# RS232.net
KiCad netlist of a schematic drawn in Altium Designer
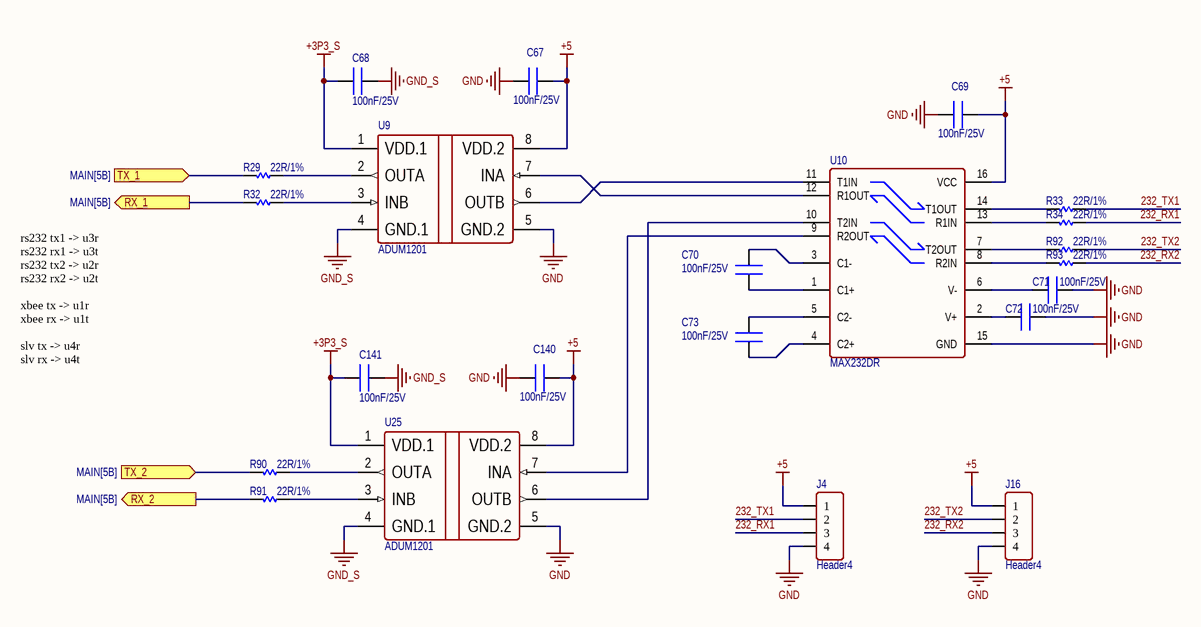
[diagram p0: RS232.SchDoc]

(export (version "E")
  (design (tool "Eeschema 10.0.6"))
  (components
    (comp (ref "C67")
      (value "100nF/25V")
      (footprint "CN-SMD-0603")
      (description "CAP CER 0.1UF 25V X7R 0603")
      (libsource (lib "Library") (part "CN"))
    )
    (comp (ref "C68")
      (value "100nF/25V")
      (footprint "CN-SMD-0603")
      (description "CAP CER 0.1UF 25V X7R 0603")
      (libsource (lib "Library") (part "CN"))
    )
    (comp (ref "C69")
      (value "100nF/25V")
      (footprint "CN-SMD-0603")
      (description "CAP CER 0.1UF 25V X7R 0603")
      (libsource (lib "Library") (part "CN"))
    )
    (comp (ref "C70")
      (value "100nF/25V")
      (footprint "CN-SMD-0603")
      (description "CAP CER 0.1UF 25V X7R 0603")
      (libsource (lib "Library") (part "CN"))
    )
    (comp (ref "C71")
      (value "100nF/25V")
      (footprint "CN-SMD-0603")
      (description "CAP CER 0.1UF 25V X7R 0603")
      (libsource (lib "Library") (part "CN"))
    )
    (comp (ref "C72")
      (value "100nF/25V")
      (footprint "CN-SMD-0603")
      (description "CAP CER 0.1UF 25V X7R 0603")
      (libsource (lib "Library") (part "CN"))
    )
    (comp (ref "C73")
      (value "100nF/25V")
      (footprint "CN-SMD-0603")
      (description "CAP CER 0.1UF 25V X7R 0603")
      (libsource (lib "Library") (part "CN"))
    )
    (comp (ref "C140")
      (value "100nF/25V")
      (footprint "CN-SMD-0603")
      (description "CAP CER 0.1UF 25V X7R 0603")
      (libsource (lib "Library") (part "CN"))
    )
    (comp (ref "C141")
      (value "100nF/25V")
      (footprint "CN-SMD-0603")
      (description "CAP CER 0.1UF 25V X7R 0603")
      (libsource (lib "Library") (part "CN"))
    )
    (comp (ref "J4")
      (value "Header4")
      (footprint "XH2.54-4-DIP")
      (description "Connector 4")
      (fields
        (field (name "MANUFACTURER") "Würth Elektronik eiSos GmbH")
        (field (name "PARTNO") "613002143121")
        (field (name "CREATED BY") "Karrer Zheng")
      )
      (libsource (lib "Library") (part "Header4"))
    )
    (comp (ref "J16")
      (value "Header4")
      (footprint "XH2.54-4-DIP")
      (description "Connector 4")
      (fields
        (field (name "MANUFACTURER") "Würth Elektronik eiSos GmbH")
        (field (name "PARTNO") "613002143121")
        (field (name "CREATED BY") "Karrer Zheng")
      )
      (libsource (lib "Library") (part "Header4"))
    )
    (comp (ref "R29")
      (value "22R/1%")
      (footprint "RES-SMD-0603")
      (description "RES SMD 22 OHM 1% 1/10W 0603")
      (libsource (lib "Library") (part "Res-SMD"))
    )
    (comp (ref "R32")
      (value "22R/1%")
      (footprint "RES-SMD-0603")
      (description "RES SMD 22 OHM 1% 1/10W 0603")
      (libsource (lib "Library") (part "Res-SMD"))
    )
    (comp (ref "R33")
      (value "22R/1%")
      (footprint "RES-SMD-0603")
      (description "RES SMD 22 OHM 1% 1/10W 0603")
      (libsource (lib "Library") (part "Res-SMD"))
    )
    (comp (ref "R34")
      (value "22R/1%")
      (footprint "RES-SMD-0603")
      (description "RES SMD 22 OHM 1% 1/10W 0603")
      (libsource (lib "Library") (part "Res-SMD"))
    )
    (comp (ref "R90")
      (value "22R/1%")
      (footprint "RES-SMD-0603")
      (description "RES SMD 22 OHM 1% 1/10W 0603")
      (libsource (lib "Library") (part "Res-SMD"))
    )
    (comp (ref "R91")
      (value "22R/1%")
      (footprint "RES-SMD-0603")
      (description "RES SMD 22 OHM 1% 1/10W 0603")
      (libsource (lib "Library") (part "Res-SMD"))
    )
    (comp (ref "R92")
      (value "22R/1%")
      (footprint "RES-SMD-0603")
      (description "RES SMD 22 OHM 1% 1/10W 0603")
      (libsource (lib "Library") (part "Res-SMD"))
    )
    (comp (ref "R93")
      (value "22R/1%")
      (footprint "RES-SMD-0603")
      (description "RES SMD 22 OHM 1% 1/10W 0603")
      (libsource (lib "Library") (part "Res-SMD"))
    )
    (comp (ref "U9")
      (value "ADUM1201")
      (footprint "SO8")
      (description "DGTL ISOLTR 2.5KV 2CH GP 8-SOIC")
      (libsource (lib "Library") (part "ADUM1201"))
    )
    (comp (ref "U10")
      (value "MAX232DR")
      (footprint "SO16")
      (description "IC TRANSCEIVER FULL 2/2 16SOIC")
      (libsource (lib "Library") (part "MAX3232"))
    )
    (comp (ref "U25")
      (value "ADUM1201")
      (footprint "SO8")
      (description "DGTL ISOLTR 2.5KV 2CH GP 8-SOIC")
      (libsource (lib "Library") (part "ADUM1201"))
    )
  )
  (nets
    (net (code "1") (name "+3P3_S") (class "Default")
      (node (ref "C141") (pin "2") (pinfunction "2_2") (pintype "passive"))
      (node (ref "C68") (pin "2") (pinfunction "2_2") (pintype "passive"))
      (node (ref "U25") (pin "1") (pinfunction "VDD.1_1") (pintype "passive"))
      (node (ref "U9") (pin "1") (pinfunction "VDD.1_1") (pintype "passive"))
    )
    (net (code "2") (name "+5") (class "Default")
      (node (ref "C140") (pin "1") (pinfunction "1_1") (pintype "passive"))
      (node (ref "C67") (pin "1") (pinfunction "1_1") (pintype "passive"))
      (node (ref "C69") (pin "1") (pinfunction "1_1") (pintype "passive"))
      (node (ref "J16") (pin "1") (pinfunction "1_1") (pintype "passive"))
      (node (ref "J4") (pin "1") (pinfunction "1_1") (pintype "passive"))
      (node (ref "U10") (pin "16") (pinfunction "VCC_16") (pintype "power_in"))
      (node (ref "U25") (pin "8") (pinfunction "VDD.2_8") (pintype "passive"))
      (node (ref "U9") (pin "8") (pinfunction "VDD.2_8") (pintype "passive"))
    )
    (net (code "3") (name "/232_RX1") (class "Default")
      (node (ref "J4") (pin "3") (pinfunction "3_3") (pintype "passive"))
      (node (ref "R34") (pin "1") (pinfunction "1_1") (pintype "passive"))
    )
    (net (code "4") (name "/232_RX2") (class "Default")
      (node (ref "J16") (pin "3") (pinfunction "3_3") (pintype "passive"))
      (node (ref "R93") (pin "1") (pinfunction "1_1") (pintype "passive"))
    )
    (net (code "5") (name "/232_TX1") (class "Default")
      (node (ref "J4") (pin "2") (pinfunction "2_2") (pintype "passive"))
      (node (ref "R33") (pin "1") (pinfunction "1_1") (pintype "passive"))
    )
    (net (code "6") (name "/232_TX2") (class "Default")
      (node (ref "J16") (pin "2") (pinfunction "2_2") (pintype "passive"))
      (node (ref "R92") (pin "1") (pinfunction "1_1") (pintype "passive"))
    )
    (net (code "7") (name "/RX_1") (class "Default")
      (node (ref "R32") (pin "2") (pinfunction "2_2") (pintype "passive"))
    )
    (net (code "8") (name "/RX_2") (class "Default")
      (node (ref "R91") (pin "2") (pinfunction "2_2") (pintype "passive"))
    )
    (net (code "9") (name "/TX_1") (class "Default")
      (node (ref "R29") (pin "2") (pinfunction "2_2") (pintype "passive"))
    )
    (net (code "10") (name "/TX_2") (class "Default")
      (node (ref "R90") (pin "2") (pinfunction "2_2") (pintype "passive"))
    )
    (net (code "11") (name "GND") (class "Default")
      (node (ref "C140") (pin "2") (pinfunction "2_2") (pintype "passive"))
      (node (ref "C67") (pin "2") (pinfunction "2_2") (pintype "passive"))
      (node (ref "C69") (pin "2") (pinfunction "2_2") (pintype "passive"))
      (node (ref "C71") (pin "1") (pinfunction "1_1") (pintype "passive"))
      (node (ref "C72") (pin "1") (pinfunction "1_1") (pintype "passive"))
      (node (ref "J16") (pin "4") (pinfunction "4_4") (pintype "passive"))
      (node (ref "J4") (pin "4") (pinfunction "4_4") (pintype "passive"))
      (node (ref "U10") (pin "15") (pinfunction "GND_15") (pintype "power_in"))
      (node (ref "U25") (pin "5") (pinfunction "GND.2_5") (pintype "passive"))
      (node (ref "U9") (pin "5") (pinfunction "GND.2_5") (pintype "passive"))
    )
    (net (code "12") (name "GND_S") (class "Default")
      (node (ref "C141") (pin "1") (pinfunction "1_1") (pintype "passive"))
      (node (ref "C68") (pin "1") (pinfunction "1_1") (pintype "passive"))
      (node (ref "U25") (pin "4") (pinfunction "GND.1_4") (pintype "passive"))
      (node (ref "U9") (pin "4") (pinfunction "GND.1_4") (pintype "passive"))
    )
    (net (code "13") (name "Net-(U9-INB)") (class "Default")
      (node (ref "R32") (pin "1") (pinfunction "1_1") (pintype "passive"))
      (node (ref "U9") (pin "3") (pinfunction "INB_3") (pintype "input"))
    )
    (net (code "14") (name "Net-(U9-OUTA)") (class "Default")
      (node (ref "R29") (pin "1") (pinfunction "1_1") (pintype "passive"))
      (node (ref "U9") (pin "2") (pinfunction "OUTA_2") (pintype "output"))
    )
    (net (code "15") (name "Net-(U10-C1+)") (class "Default")
      (node (ref "C70") (pin "1") (pinfunction "1_1") (pintype "passive"))
      (node (ref "U10") (pin "1") (pinfunction "C1+_1") (pintype "power_in"))
    )
    (net (code "16") (name "Net-(U10-C1-)") (class "Default")
      (node (ref "C70") (pin "2") (pinfunction "2_2") (pintype "passive"))
      (node (ref "U10") (pin "3") (pinfunction "C1-_3") (pintype "passive"))
    )
    (net (code "17") (name "Net-(U10-C2+)") (class "Default")
      (node (ref "C73") (pin "1") (pinfunction "1_1") (pintype "passive"))
      (node (ref "U10") (pin "4") (pinfunction "C2+_4") (pintype "passive"))
    )
    (net (code "18") (name "Net-(U10-C2-)") (class "Default")
      (node (ref "C73") (pin "2") (pinfunction "2_2") (pintype "passive"))
      (node (ref "U10") (pin "5") (pinfunction "C2-_5") (pintype "power_in"))
    )
    (net (code "19") (name "Net-(U10-R1IN)") (class "Default")
      (node (ref "R34") (pin "2") (pinfunction "2_2") (pintype "passive"))
      (node (ref "U10") (pin "13") (pinfunction "R1IN_13") (pintype "passive"))
    )
    (net (code "20") (name "Net-(U10-R1OUT)") (class "Default")
      (node (ref "U10") (pin "12") (pinfunction "R1OUT_12") (pintype "passive"))
      (node (ref "U9") (pin "7") (pinfunction "INA_7") (pintype "input"))
    )
    (net (code "21") (name "Net-(U10-R2IN)") (class "Default")
      (node (ref "R93") (pin "2") (pinfunction "2_2") (pintype "passive"))
      (node (ref "U10") (pin "8") (pinfunction "R2IN_8") (pintype "passive"))
    )
    (net (code "22") (name "Net-(U10-R2OUT)") (class "Default")
      (node (ref "U10") (pin "9") (pinfunction "R2OUT_9") (pintype "passive"))
      (node (ref "U25") (pin "7") (pinfunction "INA_7") (pintype "input"))
    )
    (net (code "23") (name "Net-(U10-T1IN)") (class "Default")
      (node (ref "U10") (pin "11") (pinfunction "T1IN_11") (pintype "passive"))
      (node (ref "U9") (pin "6") (pinfunction "OUTB_6") (pintype "output"))
    )
    (net (code "24") (name "Net-(U10-T1OUT)") (class "Default")
      (node (ref "R33") (pin "2") (pinfunction "2_2") (pintype "passive"))
      (node (ref "U10") (pin "14") (pinfunction "T1OUT_14") (pintype "power_in"))
    )
    (net (code "25") (name "Net-(U10-T2IN)") (class "Default")
      (node (ref "U10") (pin "10") (pinfunction "T2IN_10") (pintype "passive"))
      (node (ref "U25") (pin "6") (pinfunction "OUTB_6") (pintype "output"))
    )
    (net (code "26") (name "Net-(U10-T2OUT)") (class "Default")
      (node (ref "R92") (pin "2") (pinfunction "2_2") (pintype "passive"))
      (node (ref "U10") (pin "7") (pinfunction "T2OUT_7") (pintype "passive"))
    )
    (net (code "27") (name "Net-(U10-V+)") (class "Default")
      (node (ref "C72") (pin "2") (pinfunction "2_2") (pintype "passive"))
      (node (ref "U10") (pin "2") (pinfunction "V+_2") (pintype "passive"))
    )
    (net (code "28") (name "Net-(U10-V-)") (class "Default")
      (node (ref "C71") (pin "2") (pinfunction "2_2") (pintype "passive"))
      (node (ref "U10") (pin "6") (pinfunction "V-_6") (pintype "passive"))
    )
    (net (code "29") (name "Net-(U25-INB)") (class "Default")
      (node (ref "R91") (pin "1") (pinfunction "1_1") (pintype "passive"))
      (node (ref "U25") (pin "3") (pinfunction "INB_3") (pintype "input"))
    )
    (net (code "30") (name "Net-(U25-OUTA)") (class "Default")
      (node (ref "R90") (pin "1") (pinfunction "1_1") (pintype "passive"))
      (node (ref "U25") (pin "2") (pinfunction "OUTA_2") (pintype "output"))
    )
  )
)
